# SH2-MCU.net
KiCad netlist of a schematic drawn in Altium Designer
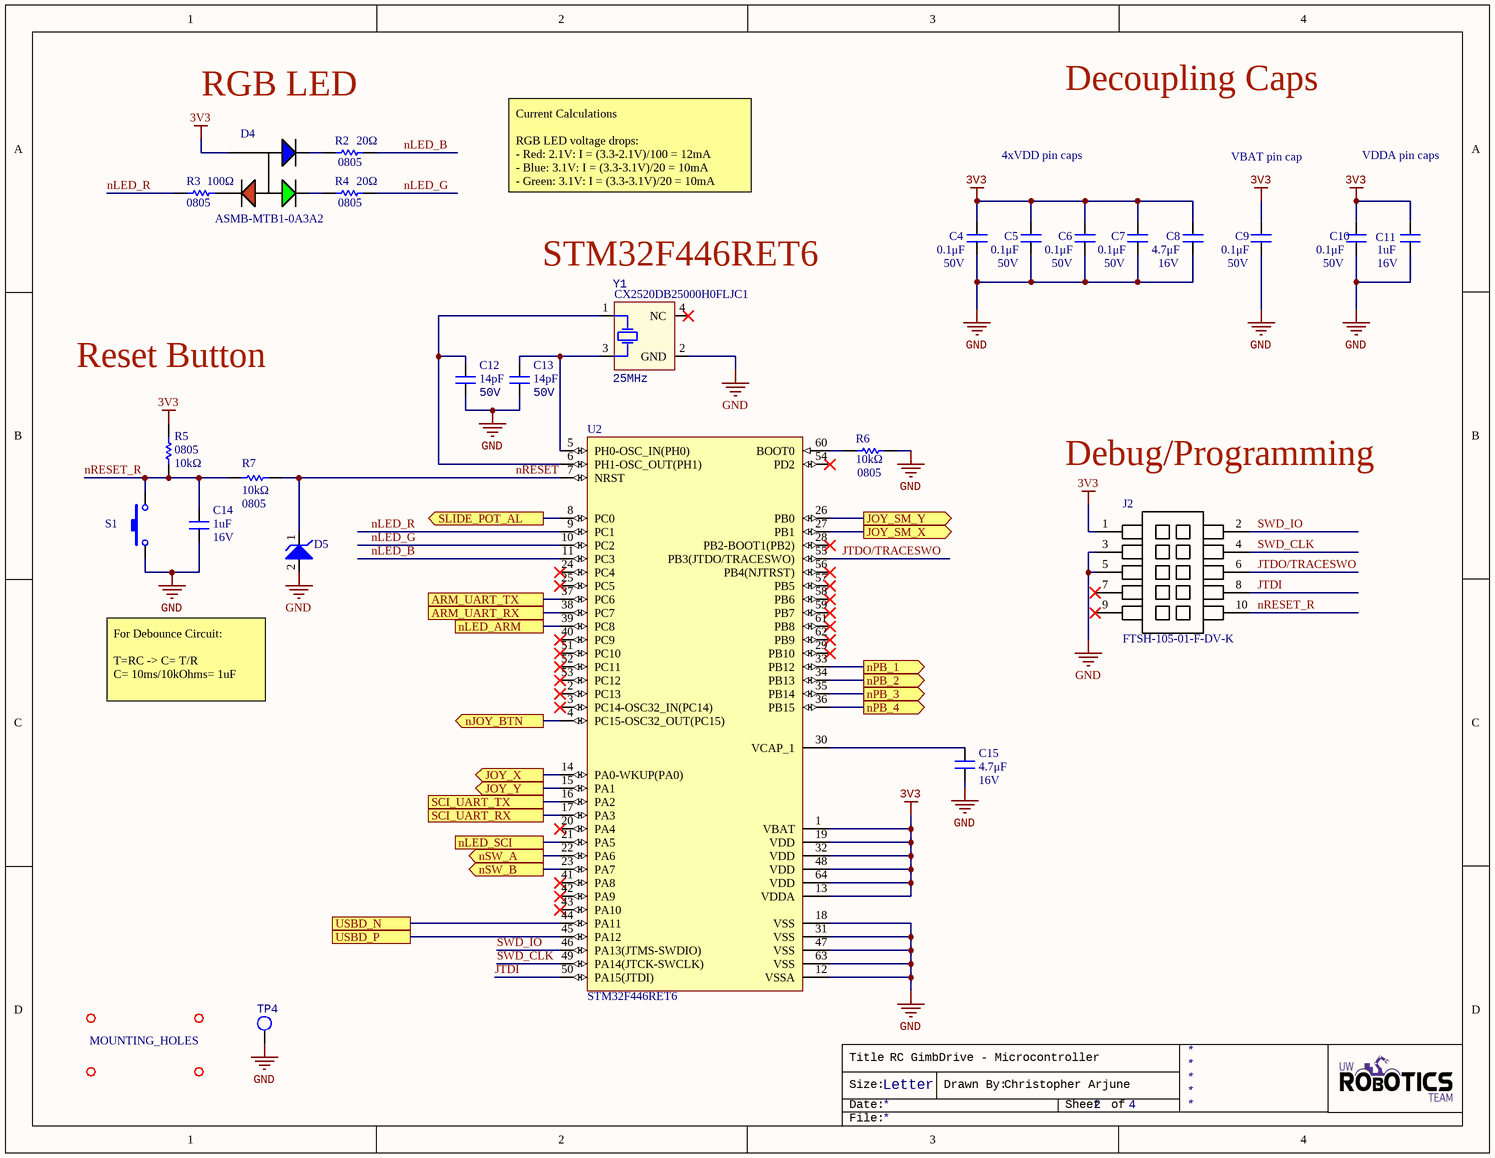
[diagram p0: SH2-MCU.SchDoc]

(export (version "E")
  (design (tool "Eeschema 10.0.6"))
  (components
    (comp (ref "C4")
      (value "0.1μF")
      (footprint "CAPC2012X140N")
      (description "CAP CER 0.1UF 50V X7R 0805")
      (fields (field (name "TOLERANCE") "10%") (field (name "VOLTAGE RATING") "50V"))
      (libsource (lib "UWRT_Schematic_Library_2020") (part "CAP_0.1uF_50V_0805"))
    )
    (comp (ref "C5")
      (value "0.1μF")
      (footprint "CAPC2012X140N")
      (description "CAP CER 0.1UF 50V X7R 0805")
      (fields (field (name "TOLERANCE") "10%") (field (name "VOLTAGE RATING") "50V"))
      (libsource (lib "UWRT_Schematic_Library_2020") (part "CAP_0.1uF_50V_0805"))
    )
    (comp (ref "C6")
      (value "0.1μF")
      (footprint "CAPC2012X140N")
      (description "CAP CER 0.1UF 50V X7R 0805")
      (fields (field (name "TOLERANCE") "10%") (field (name "VOLTAGE RATING") "50V"))
      (libsource (lib "UWRT_Schematic_Library_2020") (part "CAP_0.1uF_50V_0805"))
    )
    (comp (ref "C7")
      (value "0.1μF")
      (footprint "CAPC2012X140N")
      (description "CAP CER 0.1UF 50V X7R 0805")
      (fields (field (name "TOLERANCE") "10%") (field (name "VOLTAGE RATING") "50V"))
      (libsource (lib "UWRT_Schematic_Library_2020") (part "CAP_0.1uF_50V_0805"))
    )
    (comp (ref "C8")
      (value "4.7μF")
      (footprint "CAPC2012X140N")
      (description "CAP CER 4.7UF 16V X5R 0805")
      (fields
        (field (name "TOLERANCE") "10%")
        (field (name "VOLTAGE RATING") "16V")
        (field (name "Comment") "CAP_4.7uF_16V_0805")
      )
      (libsource (lib "UWRT_Schematic_Library_2020") (part "CAP_4.7uF_16V_0805"))
    )
    (comp (ref "C9")
      (value "0.1μF")
      (footprint "CAPC2012X140N")
      (description "CAP CER 0.1UF 50V X7R 0805")
      (fields (field (name "TOLERANCE") "10%") (field (name "VOLTAGE RATING") "50V"))
      (libsource (lib "UWRT_Schematic_Library_2020") (part "CAP_0.1uF_50V_0805"))
    )
    (comp (ref "C10")
      (value "0.1μF")
      (footprint "CAPC2012X140N")
      (description "CAP CER 0.1UF 50V X7R 0805")
      (fields (field (name "TOLERANCE") "10%") (field (name "VOLTAGE RATING") "50V"))
      (libsource (lib "UWRT_Schematic_Library_2020") (part "CAP_0.1uF_50V_0805"))
    )
    (comp (ref "C11")
      (value "1uF")
      (footprint "CAPC2012X140N")
      (description "CAP CER 1UF 16V X7R 0805")
      (fields
        (field (name "TOLERANCE") "10%")
        (field (name "VOLTAGE RATING") "16V")
        (field (name "Comment") "CAP_1uF_16V_0805")
      )
      (libsource (lib "UWRT_Schematic_Library_2020") (part "CAP_1uF_16V_0805"))
    )
    (comp (ref "C12")
      (value "14pF")
      (footprint "CAPC0603(1608)55_N")
      (description "Cap Ceramic 14pF 50V C0G 5% SMD 0603 125C Cardboard T/R")
      (fields
        (field (name "TOLERANCE") "5%")
        (field (name "VOLTAGE RATING (DC)") "50V")
        (field (name "Comment") "CL10C140JB8NNNC")
      )
      (libsource (lib "UWRT_Schematic_Library_2020") (part "CL10C140JB8NNNC"))
    )
    (comp (ref "C13")
      (value "14pF")
      (footprint "CAPC0603(1608)55_N")
      (description "Cap Ceramic 14pF 50V C0G 5% SMD 0603 125C Cardboard T/R")
      (fields
        (field (name "TOLERANCE") "5%")
        (field (name "VOLTAGE RATING (DC)") "50V")
        (field (name "Comment") "CL10C140JB8NNNC")
      )
      (libsource (lib "UWRT_Schematic_Library_2020") (part "CL10C140JB8NNNC"))
    )
    (comp (ref "C14")
      (value "1uF")
      (footprint "CAPC2012X140N")
      (description "CAP CER 1UF 16V X7R 0805")
      (fields
        (field (name "TOLERANCE") "10%")
        (field (name "VOLTAGE RATING") "16V")
        (field (name "Comment") "CAP_1uF_16V_0805")
      )
      (libsource (lib "UWRT_Schematic_Library_2020") (part "CAP_1uF_16V_0805"))
    )
    (comp (ref "C15")
      (value "4.7μF")
      (footprint "CAPC2012X140N")
      (description "CAP CER 4.7UF 16V X5R 0805")
      (fields
        (field (name "TOLERANCE") "10%")
        (field (name "VOLTAGE RATING") "16V")
        (field (name "Comment") "CAP_4.7uF_16V_0805")
      )
      (libsource (lib "UWRT_Schematic_Library_2020") (part "CAP_4.7uF_16V_0805"))
    )
    (comp (ref "D4")
      (value "LED_RGB")
      (footprint "LED_RGB")
      (description "LED RGB DIFFUSED 4PLCC SMD")
      (fields (field (name "MANUFACTURER PART NUMBER 1") "ASMB-MTB1-0A3A2"))
      (libsource (lib "UWRT_Schematic_Library_2020") (part "LED_RGB"))
    )
    (comp (ref "D5")
      (value "TVS_DIODE_UNIDIR_3.3V")
      (footprint "SOD523")
      (description "TVS DIODE 3.3V 14.1V SOD523. Used to protect each connector input line going into the MCU.")
      (libsource (lib "UWRT_Schematic_Library_2020") (part "TVS_DIODE_UNIDIR_3.3V"))
    )
    (comp (ref "J2")
      (value "CON_PROGRAMMING")
      (footprint "FTSH-105-01-F-DV-K-P-TR")
      (fields (field (name "MANUFACTURER PART NUMBER 1") "FTSH-105-01-F-DV-K"))
      (libsource (lib "UWRT_Schematic_Library_2020") (part "CON_PROGRAMMING"))
    )
    (comp (ref "MH1")
      (value "MOUNTING_HOLES")
      (footprint "MOUNTING_HOLE")
      (description "6cm x 6cm")
      (libsource (lib "UWRT_Schematic_Library_2020") (part "MOUNTING_HOLES"))
    )
    (comp (ref "MH2")
      (value "MOUNTING_HOLES")
      (footprint "MOUNTING_HOLE")
      (description "6cm x 6cm")
      (libsource (lib "UWRT_Schematic_Library_2020") (part "MOUNTING_HOLES"))
    )
    (comp (ref "MH3")
      (value "MOUNTING_HOLES")
      (footprint "MOUNTING_HOLE")
      (description "6cm x 6cm")
      (libsource (lib "UWRT_Schematic_Library_2020") (part "MOUNTING_HOLES"))
    )
    (comp (ref "MH4")
      (value "MOUNTING_HOLES")
      (footprint "MOUNTING_HOLE")
      (description "6cm x 6cm")
      (libsource (lib "UWRT_Schematic_Library_2020") (part "MOUNTING_HOLES"))
    )
    (comp (ref "R2")
      (value "20Ω")
      (footprint "RESC2012X60N")
      (description "RES SMD 20 OHM 1% 1/8W 0805")
      (fields
        (field (name "CASE CODE (IMPERIAL)") "0805")
        (field (name "TOLERANCE") "1%")
        (field (name "Comment") "RES_20Ω_0805")
      )
      (libsource (lib "UWRT_Schematic_Library_2020") (part "RES_20Ω_0805"))
    )
    (comp (ref "R3")
      (value "100Ω")
      (footprint "RESC2012X60N")
      (description "RES SMD 100 OHM 1% 1/8W 0805")
      (fields (field (name "CASE CODE (IMPERIAL)") "0805") (field (name "Comment") "RES_100Ω_0805"))
      (libsource (lib "UWRT_Schematic_Library_2020") (part "RES_100Ω_0805"))
    )
    (comp (ref "R4")
      (value "20Ω")
      (footprint "RESC2012X60N")
      (description "RES SMD 20 OHM 1% 1/8W 0805")
      (fields
        (field (name "CASE CODE (IMPERIAL)") "0805")
        (field (name "TOLERANCE") "1%")
        (field (name "Comment") "RES_20Ω_0805")
      )
      (libsource (lib "UWRT_Schematic_Library_2020") (part "RES_20Ω_0805"))
    )
    (comp (ref "R5")
      (value "10kΩ")
      (footprint "RESC2012X60N")
      (description "RES SMD 10K OHM 1% 1/8W 0805")
      (fields
        (field (name "CASE CODE (IMPERIAL)") "0805")
        (field (name "TOLERANCE") "1%")
        (field (name "Comment") "RES_10kΩ_0805")
      )
      (libsource (lib "UWRT_Schematic_Library_2020") (part "RES_10kΩ_0805"))
    )
    (comp (ref "R6")
      (value "10kΩ")
      (footprint "RESC2012X60N")
      (description "RES SMD 10K OHM 1% 1/8W 0805")
      (fields
        (field (name "CASE CODE (IMPERIAL)") "0805")
        (field (name "TOLERANCE") "1%")
        (field (name "Comment") "RES_10kΩ_0805")
      )
      (libsource (lib "UWRT_Schematic_Library_2020") (part "RES_10kΩ_0805"))
    )
    (comp (ref "R7")
      (value "10kΩ")
      (footprint "RESC2012X60N")
      (description "RES SMD 10K OHM 1% 1/8W 0805")
      (fields
        (field (name "CASE CODE (IMPERIAL)") "0805")
        (field (name "TOLERANCE") "1%")
        (field (name "Comment") "RES_10kΩ_0805")
      )
      (libsource (lib "UWRT_Schematic_Library_2020") (part "RES_10kΩ_0805"))
    )
    (comp (ref "S1")
      (value "SW_TACTILE")
      (footprint "B3U-1000P")
      (description "Tactile Switch (Grey)")
      (libsource (lib "UWRT_Schematic_Library_2020") (part "SW_TACTILE"))
    )
    (comp (ref "TP4")
      (value "TESTPOINT_LOOP")
      (footprint "TESTPOINT_LOOP")
      (description "Loop testpoint through-hole pad")
      (libsource (lib "UWRT_Schematic_Library_2020") (part "TESTPOINT_LOOP"))
    )
    (comp (ref "U2")
      (value "STM32F446RET6")
      (footprint "STM-LQFP64_L")
      (libsource (lib "UWRT_Schematic_Library_2020") (part "MCU_STM32F446RET6"))
    )
    (comp (ref "Y1")
      (value "CRYSTAL_25MHZ")
      (footprint "SOIC254P1016X440-4N")
      (description "CRYSTAL 25.0000MHZ 12PF SMD")
      (fields
        (field (name "MANUFACTURER PART NUMBER 1") "CX2520DB25000H0FLJC1")
        (field (name "FREQUENCY") "25MHz")
      )
      (libsource (lib "UWRT_Schematic_Library_2020") (part "CRYSTAL_25MHZ"))
    )
  )
  (nets
    (net (code "1") (name "/ARM_UART_RX") (class "Default")
      (node (ref "U2") (pin "38") (pinfunction "PC7_38") (pintype "bidirectional"))
    )
    (net (code "2") (name "/ARM_UART_TX") (class "Default")
      (node (ref "U2") (pin "37") (pinfunction "PC6_37") (pintype "bidirectional"))
    )
    (net (code "3") (name "/JOY_SM_X") (class "Default")
      (node (ref "U2") (pin "27") (pinfunction "PB1_27") (pintype "bidirectional"))
    )
    (net (code "4") (name "/JOY_SM_Y") (class "Default")
      (node (ref "U2") (pin "26") (pinfunction "PB0_26") (pintype "bidirectional"))
    )
    (net (code "5") (name "/JOY_X") (class "Default")
      (node (ref "U2") (pin "14") (pinfunction "PA0-WKUP(PA0)_14") (pintype "bidirectional"))
    )
    (net (code "6") (name "/JOY_Y") (class "Default")
      (node (ref "U2") (pin "15") (pinfunction "PA1_15") (pintype "bidirectional"))
    )
    (net (code "7") (name "/JTDI") (class "Default")
      (node (ref "J2") (pin "8") (pinfunction "8_8") (pintype "passive"))
      (node (ref "U2") (pin "50") (pinfunction "PA15(JTDI)_50") (pintype "bidirectional"))
    )
    (net (code "8") (name "/JTDO{slash}TRACESWO") (class "Default")
      (node (ref "J2") (pin "6") (pinfunction "6_6") (pintype "passive"))
      (node (ref "U2") (pin "55") (pinfunction "PB3(JTDO/TRACESWO)_55") (pintype "bidirectional"))
    )
    (net (code "9") (name "/SCI_UART_RX") (class "Default")
      (node (ref "U2") (pin "17") (pinfunction "PA3_17") (pintype "bidirectional"))
    )
    (net (code "10") (name "/SCI_UART_TX") (class "Default")
      (node (ref "U2") (pin "16") (pinfunction "PA2_16") (pintype "bidirectional"))
    )
    (net (code "11") (name "/SLIDE_POT_AL") (class "Default")
      (node (ref "U2") (pin "8") (pinfunction "PC0_8") (pintype "bidirectional"))
    )
    (net (code "12") (name "/SWD_CLK") (class "Default")
      (node (ref "J2") (pin "4") (pinfunction "4_4") (pintype "passive"))
      (node (ref "U2") (pin "49") (pinfunction "PA14(JTCK-SWCLK)_49") (pintype "bidirectional"))
    )
    (net (code "13") (name "/SWD_IO") (class "Default")
      (node (ref "J2") (pin "2") (pinfunction "2_2") (pintype "passive"))
      (node (ref "U2") (pin "46") (pinfunction "PA13(JTMS-SWDIO)_46") (pintype "bidirectional"))
    )
    (net (code "14") (name "/USBD_N") (class "Default")
      (node (ref "U2") (pin "44") (pinfunction "PA11_44") (pintype "bidirectional"))
    )
    (net (code "15") (name "/USBD_P") (class "Default")
      (node (ref "U2") (pin "45") (pinfunction "PA12_45") (pintype "bidirectional"))
    )
    (net (code "16") (name "/nJOY_BTN") (class "Default")
      (node (ref "U2") (pin "4") (pinfunction "PC15-OSC32_OUT(PC15)_4") (pintype "bidirectional"))
    )
    (net (code "17") (name "/nLED_ARM") (class "Default")
      (node (ref "U2") (pin "39") (pinfunction "PC8_39") (pintype "bidirectional"))
    )
    (net (code "18") (name "/nLED_B") (class "Default")
      (node (ref "R2") (pin "2") (pinfunction "2_2") (pintype "passive"))
      (node (ref "U2") (pin "11") (pinfunction "PC3_11") (pintype "bidirectional"))
    )
    (net (code "19") (name "/nLED_G") (class "Default")
      (node (ref "R4") (pin "2") (pinfunction "2_2") (pintype "passive"))
      (node (ref "U2") (pin "10") (pinfunction "PC2_10") (pintype "bidirectional"))
    )
    (net (code "20") (name "/nLED_R") (class "Default")
      (node (ref "R3") (pin "1") (pinfunction "1_1") (pintype "passive"))
      (node (ref "U2") (pin "9") (pinfunction "PC1_9") (pintype "bidirectional"))
    )
    (net (code "21") (name "/nLED_SCI") (class "Default")
      (node (ref "U2") (pin "21") (pinfunction "PA5_21") (pintype "bidirectional"))
    )
    (net (code "22") (name "/nPB_1") (class "Default")
      (node (ref "U2") (pin "33") (pinfunction "PB12_33") (pintype "bidirectional"))
    )
    (net (code "23") (name "/nPB_2") (class "Default")
      (node (ref "U2") (pin "34") (pinfunction "PB13_34") (pintype "bidirectional"))
    )
    (net (code "24") (name "/nPB_3") (class "Default")
      (node (ref "U2") (pin "35") (pinfunction "PB14_35") (pintype "bidirectional"))
    )
    (net (code "25") (name "/nPB_4") (class "Default")
      (node (ref "U2") (pin "36") (pinfunction "PB15_36") (pintype "bidirectional"))
    )
    (net (code "26") (name "/nRESET") (class "Default")
      (node (ref "D5") (pin "1") (pinfunction "1_1") (pintype "passive"))
      (node (ref "R7") (pin "2") (pinfunction "2_2") (pintype "passive"))
      (node (ref "U2") (pin "7") (pinfunction "NRST_7") (pintype "bidirectional"))
    )
    (net (code "27") (name "/nRESET_R") (class "Default")
      (node (ref "C14") (pin "2") (pinfunction "2_2") (pintype "passive"))
      (node (ref "J2") (pin "10") (pinfunction "10_10") (pintype "passive"))
      (node (ref "R5") (pin "1") (pinfunction "1_1") (pintype "passive"))
      (node (ref "R7") (pin "1") (pinfunction "1_1") (pintype "passive"))
      (node (ref "S1") (pin "1") (pinfunction "1_1") (pintype "passive"))
    )
    (net (code "28") (name "/nSW_A") (class "Default")
      (node (ref "U2") (pin "22") (pinfunction "PA6_22") (pintype "bidirectional"))
    )
    (net (code "29") (name "/nSW_B") (class "Default")
      (node (ref "U2") (pin "23") (pinfunction "PA7_23") (pintype "bidirectional"))
    )
    (net (code "30") (name "3V3") (class "Default")
      (node (ref "C10") (pin "2") (pinfunction "2_2") (pintype "passive"))
      (node (ref "C11") (pin "2") (pinfunction "2_2") (pintype "passive"))
      (node (ref "C4") (pin "2") (pinfunction "2_2") (pintype "passive"))
      (node (ref "C5") (pin "2") (pinfunction "2_2") (pintype "passive"))
      (node (ref "C6") (pin "2") (pinfunction "2_2") (pintype "passive"))
      (node (ref "C7") (pin "2") (pinfunction "2_2") (pintype "passive"))
      (node (ref "C8") (pin "2") (pinfunction "2_2") (pintype "passive"))
      (node (ref "C9") (pin "2") (pinfunction "2_2") (pintype "passive"))
      (node (ref "D4") (pin "4") (pinfunction "9_4") (pintype "passive"))
      (node (ref "J2") (pin "1") (pinfunction "1_1") (pintype "passive"))
      (node (ref "R5") (pin "2") (pinfunction "2_2") (pintype "passive"))
      (node (ref "U2") (pin "1") (pinfunction "VBAT_1") (pintype "power_in"))
      (node (ref "U2") (pin "13") (pinfunction "VDDA_13") (pintype "power_in"))
      (node (ref "U2") (pin "19") (pinfunction "VDD_19") (pintype "power_in"))
      (node (ref "U2") (pin "32") (pinfunction "VDD_32") (pintype "power_in"))
      (node (ref "U2") (pin "48") (pinfunction "VDD_48") (pintype "power_in"))
      (node (ref "U2") (pin "64") (pinfunction "VDD_64") (pintype "power_in"))
    )
    (net (code "31") (name "GND") (class "Default")
      (node (ref "C10") (pin "1") (pinfunction "1_1") (pintype "passive"))
      (node (ref "C11") (pin "1") (pinfunction "1_1") (pintype "passive"))
      (node (ref "C12") (pin "1") (pinfunction "1_1") (pintype "passive"))
      (node (ref "C13") (pin "1") (pinfunction "1_1") (pintype "passive"))
      (node (ref "C14") (pin "1") (pinfunction "1_1") (pintype "passive"))
      (node (ref "C15") (pin "1") (pinfunction "1_1") (pintype "passive"))
      (node (ref "C4") (pin "1") (pinfunction "1_1") (pintype "passive"))
      (node (ref "C5") (pin "1") (pinfunction "1_1") (pintype "passive"))
      (node (ref "C6") (pin "1") (pinfunction "1_1") (pintype "passive"))
      (node (ref "C7") (pin "1") (pinfunction "1_1") (pintype "passive"))
      (node (ref "C8") (pin "1") (pinfunction "1_1") (pintype "passive"))
      (node (ref "C9") (pin "1") (pinfunction "1_1") (pintype "passive"))
      (node (ref "D5") (pin "2") (pinfunction "2_2") (pintype "passive"))
      (node (ref "J2") (pin "3") (pinfunction "3_3") (pintype "passive"))
      (node (ref "J2") (pin "5") (pinfunction "5_5") (pintype "passive"))
      (node (ref "R6") (pin "2") (pinfunction "2_2") (pintype "passive"))
      (node (ref "S1") (pin "2") (pinfunction "2_2") (pintype "passive"))
      (node (ref "TP4") (pin "1") (pintype "passive"))
      (node (ref "U2") (pin "12") (pinfunction "VSSA_12") (pintype "power_in"))
      (node (ref "U2") (pin "18") (pinfunction "VSS_18") (pintype "power_in"))
      (node (ref "U2") (pin "31") (pinfunction "VSS_31") (pintype "power_in"))
      (node (ref "U2") (pin "47") (pinfunction "VSS_47") (pintype "power_in"))
      (node (ref "U2") (pin "63") (pinfunction "VSS_63") (pintype "power_in"))
      (node (ref "Y1") (pin "2") (pinfunction "GND_2") (pintype "power_in"))
    )
    (net (code "32") (name "Net-(D4-10)") (class "Default")
      (node (ref "D4") (pin "3") (pinfunction "10_3") (pintype "passive"))
      (node (ref "R2") (pin "1") (pinfunction "1_1") (pintype "passive"))
    )
    (net (code "33") (name "Net-(D4-11)") (class "Default")
      (node (ref "D4") (pin "1") (pinfunction "11_1") (pintype "passive"))
      (node (ref "R3") (pin "2") (pinfunction "2_2") (pintype "passive"))
    )
    (net (code "34") (name "Net-(D4-12)") (class "Default")
      (node (ref "D4") (pin "2") (pinfunction "12_2") (pintype "passive"))
      (node (ref "R4") (pin "1") (pinfunction "1_1") (pintype "passive"))
    )
    (net (code "35") (name "Net-(U2-BOOT0)") (class "Default")
      (node (ref "R6") (pin "1") (pinfunction "1_1") (pintype "passive"))
      (node (ref "U2") (pin "60") (pinfunction "BOOT0_60") (pintype "input"))
    )
    (net (code "36") (name "Net-(U2-PH0-OSC_IN(PH0))") (class "Default")
      (node (ref "C13") (pin "2") (pinfunction "2_2") (pintype "passive"))
      (node (ref "U2") (pin "5") (pinfunction "PH0-OSC_IN(PH0)_5") (pintype "bidirectional"))
      (node (ref "Y1") (pin "3") (pinfunction "HOT_3") (pintype "passive"))
    )
    (net (code "37") (name "Net-(U2-PH1-OSC_OUT(PH1))") (class "Default")
      (node (ref "C12") (pin "2") (pinfunction "2_2") (pintype "passive"))
      (node (ref "U2") (pin "6") (pinfunction "PH1-OSC_OUT(PH1)_6") (pintype "bidirectional"))
      (node (ref "Y1") (pin "1") (pinfunction "HOT_1") (pintype "passive"))
    )
    (net (code "38") (name "Net-(U2-VCAP_1)") (class "Default")
      (node (ref "C15") (pin "2") (pinfunction "2_2") (pintype "passive"))
      (node (ref "U2") (pin "30") (pinfunction "VCAP_1_30") (pintype "passive"))
    )
    (net (code "39") (name "unconnected-(J2-Pad7)") (class "Default")
      (node (ref "J2") (pin "7") (pinfunction "7_7") (pintype "passive+no_connect"))
    )
    (net (code "40") (name "unconnected-(J2-Pad9)") (class "Default")
      (node (ref "J2") (pin "9") (pinfunction "9_9") (pintype "passive+no_connect"))
    )
    (net (code "41") (name "unconnected-(U2-PA4-Pad20)") (class "Default")
      (node (ref "U2") (pin "20") (pinfunction "PA4_20") (pintype "bidirectional+no_connect"))
    )
    (net (code "42") (name "unconnected-(U2-PA8-Pad41)") (class "Default")
      (node (ref "U2") (pin "41") (pinfunction "PA8_41") (pintype "bidirectional+no_connect"))
    )
    (net (code "43") (name "unconnected-(U2-PA9-Pad42)") (class "Default")
      (node (ref "U2") (pin "42") (pinfunction "PA9_42") (pintype "bidirectional+no_connect"))
    )
    (net (code "44") (name "unconnected-(U2-PA10-Pad43)") (class "Default")
      (node (ref "U2") (pin "43") (pinfunction "PA10_43") (pintype "bidirectional+no_connect"))
    )
    (net (code "45") (name "unconnected-(U2-PB2-BOOT1(PB2)-Pad28)") (class "Default")
      (node (ref "U2") (pin "28") (pinfunction "PB2-BOOT1(PB2)_28") (pintype "bidirectional+no_connect"))
    )
    (net (code "46") (name "unconnected-(U2-PB4(NJTRST)-Pad56)") (class "Default")
      (node (ref "U2") (pin "56") (pinfunction "PB4(NJTRST)_56") (pintype "bidirectional+no_connect"))
    )
    (net (code "47") (name "unconnected-(U2-PB5-Pad57)") (class "Default")
      (node (ref "U2") (pin "57") (pinfunction "PB5_57") (pintype "bidirectional+no_connect"))
    )
    (net (code "48") (name "unconnected-(U2-PB6-Pad58)") (class "Default")
      (node (ref "U2") (pin "58") (pinfunction "PB6_58") (pintype "bidirectional+no_connect"))
    )
    (net (code "49") (name "unconnected-(U2-PB7-Pad59)") (class "Default")
      (node (ref "U2") (pin "59") (pinfunction "PB7_59") (pintype "bidirectional+no_connect"))
    )
    (net (code "50") (name "unconnected-(U2-PB8-Pad61)") (class "Default")
      (node (ref "U2") (pin "61") (pinfunction "PB8_61") (pintype "bidirectional+no_connect"))
    )
    (net (code "51") (name "unconnected-(U2-PB9-Pad62)") (class "Default")
      (node (ref "U2") (pin "62") (pinfunction "PB9_62") (pintype "bidirectional+no_connect"))
    )
    (net (code "52") (name "unconnected-(U2-PB10-Pad29)") (class "Default")
      (node (ref "U2") (pin "29") (pinfunction "PB10_29") (pintype "bidirectional+no_connect"))
    )
    (net (code "53") (name "unconnected-(U2-PC4-Pad24)") (class "Default")
      (node (ref "U2") (pin "24") (pinfunction "PC4_24") (pintype "bidirectional+no_connect"))
    )
    (net (code "54") (name "unconnected-(U2-PC5-Pad25)") (class "Default")
      (node (ref "U2") (pin "25") (pinfunction "PC5_25") (pintype "bidirectional+no_connect"))
    )
    (net (code "55") (name "unconnected-(U2-PC9-Pad40)") (class "Default")
      (node (ref "U2") (pin "40") (pinfunction "PC9_40") (pintype "bidirectional+no_connect"))
    )
    (net (code "56") (name "unconnected-(U2-PC10-Pad51)") (class "Default")
      (node (ref "U2") (pin "51") (pinfunction "PC10_51") (pintype "bidirectional+no_connect"))
    )
    (net (code "57") (name "unconnected-(U2-PC11-Pad52)") (class "Default")
      (node (ref "U2") (pin "52") (pinfunction "PC11_52") (pintype "bidirectional+no_connect"))
    )
    (net (code "58") (name "unconnected-(U2-PC12-Pad53)") (class "Default")
      (node (ref "U2") (pin "53") (pinfunction "PC12_53") (pintype "bidirectional+no_connect"))
    )
    (net (code "59") (name "unconnected-(U2-PC13-Pad2)") (class "Default")
      (node (ref "U2") (pin "2") (pinfunction "PC13_2") (pintype "bidirectional+no_connect"))
    )
    (net (code "60") (name "unconnected-(U2-PC14-OSC32_IN(PC14)-Pad3)") (class "Default")
      (node (ref "U2") (pin "3") (pinfunction "PC14-OSC32_IN(PC14)_3") (pintype "bidirectional+no_connect"))
    )
    (net (code "61") (name "unconnected-(U2-PD2-Pad54)") (class "Default")
      (node (ref "U2") (pin "54") (pinfunction "PD2_54") (pintype "bidirectional+no_connect"))
    )
    (net (code "62") (name "unconnected-(Y1-NC-Pad4)") (class "Default")
      (node (ref "Y1") (pin "4") (pinfunction "NC_4") (pintype "passive+no_connect"))
    )
  )
)
